# Flash.net
KiCad netlist of a schematic drawn in Altium Designer
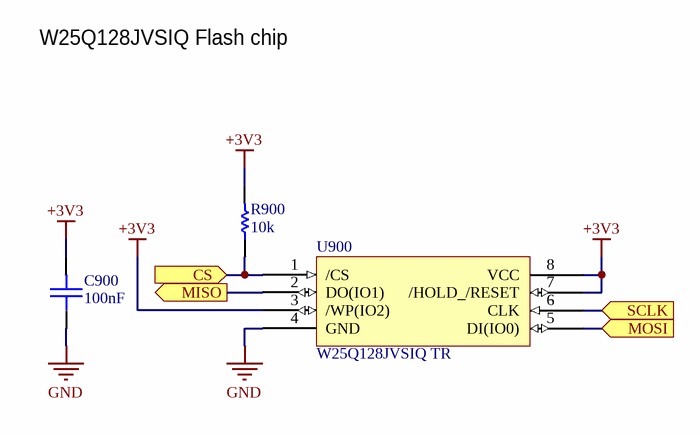
[diagram p0: Flash.SchDoc]

(export (version "E")
  (design (tool "Eeschema 10.0.6"))
  (components
    (comp (ref "C900")
      (value "100nF")
      (footprint "0603_CAP")
      (libsource (lib "Moonlight_Components") (part "Capacitor"))
    )
    (comp (ref "R900")
      (value "10k")
      (footprint "0603_RES")
      (libsource (lib "Moonlight_Components") (part "Resistor"))
    )
    (comp (ref "U900")
      (value "W25Q128JVSIQ TR")
      (footprint "SOIC_208MIL_WIN")
      (description "No Description Available")
      (fields (field (name "COPYRIGHT") "Copyright (C) 2018 Accelerated Designs. All rights reserved"))
      (libsource (lib "Moonlight_Components") (part "W25Q128JVSIQ TR"))
    )
  )
  (nets
    (net (code "1") (name "+3V3") (class "Default")
      (node (ref "C900") (pin "1") (pinfunction "1_1") (pintype "passive"))
      (node (ref "R900") (pin "2") (pinfunction "2_2") (pintype "passive"))
      (node (ref "U900") (pin "3") (pinfunction "/WP(IO2)_3") (pintype "bidirectional"))
      (node (ref "U900") (pin "7") (pinfunction "/HOLD_/RESET_7") (pintype "bidirectional"))
      (node (ref "U900") (pin "8") (pinfunction "VCC_8") (pintype "power_in"))
    )
    (net (code "2") (name "/CS") (class "Default")
      (node (ref "R900") (pin "1") (pinfunction "1_1") (pintype "passive"))
      (node (ref "U900") (pin "1") (pinfunction "/CS_1") (pintype "input"))
    )
    (net (code "3") (name "/MISO") (class "Default")
      (node (ref "U900") (pin "2") (pinfunction "DO(IO1)_2") (pintype "bidirectional"))
    )
    (net (code "4") (name "/MOSI") (class "Default")
      (node (ref "U900") (pin "5") (pinfunction "DI(IO0)_5") (pintype "bidirectional"))
    )
    (net (code "5") (name "/SCLK") (class "Default")
      (node (ref "U900") (pin "6") (pinfunction "CLK_6") (pintype "input"))
    )
    (net (code "6") (name "GND") (class "Default")
      (node (ref "C900") (pin "2") (pinfunction "2_2") (pintype "passive"))
      (node (ref "U900") (pin "4") (pinfunction "GND_4") (pintype "passive"))
    )
  )
)
